# design.net
KiCad netlist of a schematic drawn in Altium Designer
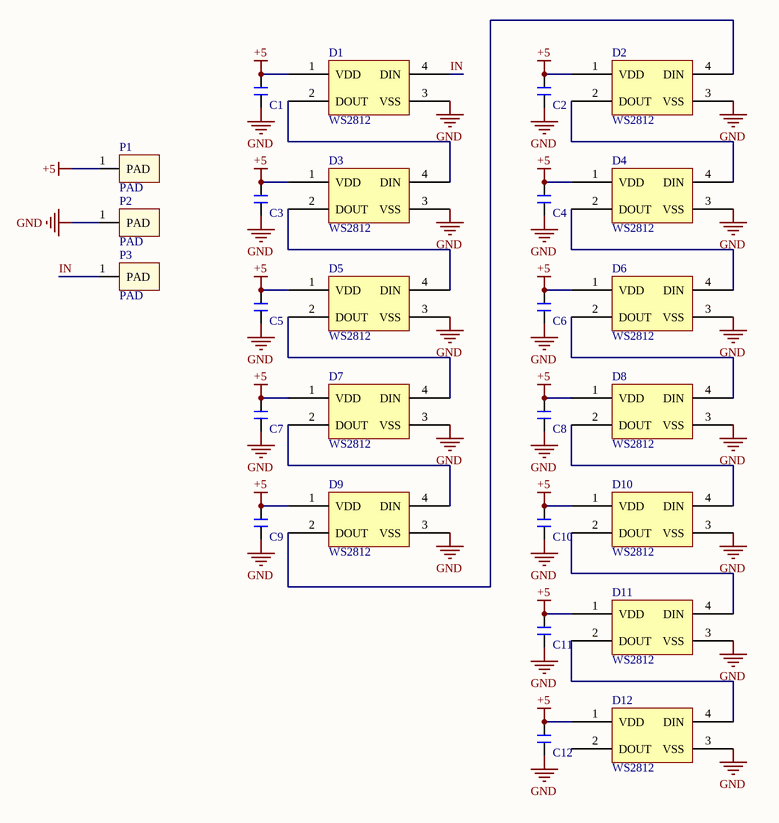
[diagram p0: 光圈图纸.SchDoc]

(export (version "E")
  (design (tool "Eeschema 10.0.6"))
  (components
    (comp (ref "C1") (value "cap") (footprint "0603c") (libsource (lib "元件库") (part "CAP")))
    (comp (ref "C2") (value "cap") (footprint "0603c") (libsource (lib "元件库") (part "CAP")))
    (comp (ref "C3") (value "cap") (footprint "0603c") (libsource (lib "元件库") (part "CAP")))
    (comp (ref "C4") (value "cap") (footprint "0603c") (libsource (lib "元件库") (part "CAP")))
    (comp (ref "C5") (value "cap") (footprint "0603c") (libsource (lib "元件库") (part "CAP")))
    (comp (ref "C6") (value "cap") (footprint "0603c") (libsource (lib "元件库") (part "CAP")))
    (comp (ref "C7") (value "cap") (footprint "0603c") (libsource (lib "元件库") (part "CAP")))
    (comp (ref "C8") (value "cap") (footprint "0603c") (libsource (lib "元件库") (part "CAP")))
    (comp (ref "C9") (value "cap") (footprint "0603c") (libsource (lib "元件库") (part "CAP")))
    (comp (ref "C10") (value "cap") (footprint "0603c") (libsource (lib "元件库") (part "CAP")))
    (comp (ref "C11") (value "cap") (footprint "0603c") (libsource (lib "元件库") (part "CAP")))
    (comp (ref "C12") (value "cap") (footprint "0603c") (libsource (lib "元件库") (part "CAP")))
    (comp (ref "D1") (value "WS2812") (footprint "WS2812") (libsource (lib "元件库") (part "WS2812")))
    (comp (ref "D2") (value "WS2812") (footprint "WS2812") (libsource (lib "元件库") (part "WS2812")))
    (comp (ref "D3") (value "WS2812") (footprint "WS2812") (libsource (lib "元件库") (part "WS2812")))
    (comp (ref "D4") (value "WS2812") (footprint "WS2812") (libsource (lib "元件库") (part "WS2812")))
    (comp (ref "D5") (value "WS2812") (footprint "WS2812") (libsource (lib "元件库") (part "WS2812")))
    (comp (ref "D6") (value "WS2812") (footprint "WS2812") (libsource (lib "元件库") (part "WS2812")))
    (comp (ref "D7") (value "WS2812") (footprint "WS2812") (libsource (lib "元件库") (part "WS2812")))
    (comp (ref "D8") (value "WS2812") (footprint "WS2812") (libsource (lib "元件库") (part "WS2812")))
    (comp (ref "D9") (value "WS2812") (footprint "WS2812") (libsource (lib "元件库") (part "WS2812")))
    (comp (ref "D10") (value "WS2812") (footprint "WS2812") (libsource (lib "元件库") (part "WS2812")))
    (comp (ref "D11") (value "WS2812") (footprint "WS2812") (libsource (lib "元件库") (part "WS2812")))
    (comp (ref "D12") (value "WS2812") (footprint "WS2812") (libsource (lib "元件库") (part "WS2812")))
    (comp (ref "P1") (value "PAD") (footprint "PAD") (libsource (lib "Schlib1") (part "PAD")))
    (comp (ref "P2") (value "PAD") (footprint "PAD") (libsource (lib "Schlib1") (part "PAD")))
    (comp (ref "P3") (value "PAD") (footprint "PAD") (libsource (lib "Schlib1") (part "PAD")))
  )
  (nets
    (net (code "1") (name "+5") (class "Default")
      (node (ref "C1") (pin "2") (pinfunction "2_2") (pintype "passive"))
      (node (ref "C10") (pin "2") (pinfunction "2_2") (pintype "passive"))
      (node (ref "C11") (pin "2") (pinfunction "2_2") (pintype "passive"))
      (node (ref "C12") (pin "2") (pinfunction "2_2") (pintype "passive"))
      (node (ref "C2") (pin "2") (pinfunction "2_2") (pintype "passive"))
      (node (ref "C3") (pin "2") (pinfunction "2_2") (pintype "passive"))
      (node (ref "C4") (pin "2") (pinfunction "2_2") (pintype "passive"))
      (node (ref "C5") (pin "2") (pinfunction "2_2") (pintype "passive"))
      (node (ref "C6") (pin "2") (pinfunction "2_2") (pintype "passive"))
      (node (ref "C7") (pin "2") (pinfunction "2_2") (pintype "passive"))
      (node (ref "C8") (pin "2") (pinfunction "2_2") (pintype "passive"))
      (node (ref "C9") (pin "2") (pinfunction "2_2") (pintype "passive"))
      (node (ref "D1") (pin "1") (pinfunction "VDD_1") (pintype "passive"))
      (node (ref "D10") (pin "1") (pinfunction "VDD_1") (pintype "passive"))
      (node (ref "D11") (pin "1") (pinfunction "VDD_1") (pintype "passive"))
      (node (ref "D12") (pin "1") (pinfunction "VDD_1") (pintype "passive"))
      (node (ref "D2") (pin "1") (pinfunction "VDD_1") (pintype "passive"))
      (node (ref "D3") (pin "1") (pinfunction "VDD_1") (pintype "passive"))
      (node (ref "D4") (pin "1") (pinfunction "VDD_1") (pintype "passive"))
      (node (ref "D5") (pin "1") (pinfunction "VDD_1") (pintype "passive"))
      (node (ref "D6") (pin "1") (pinfunction "VDD_1") (pintype "passive"))
      (node (ref "D7") (pin "1") (pinfunction "VDD_1") (pintype "passive"))
      (node (ref "D8") (pin "1") (pinfunction "VDD_1") (pintype "passive"))
      (node (ref "D9") (pin "1") (pinfunction "VDD_1") (pintype "passive"))
      (node (ref "P1") (pin "1") (pinfunction "PAD_1") (pintype "passive"))
    )
    (net (code "2") (name "/IN") (class "Default")
      (node (ref "D1") (pin "4") (pinfunction "DIN_4") (pintype "passive"))
      (node (ref "P3") (pin "1") (pinfunction "PAD_1") (pintype "passive"))
    )
    (net (code "3") (name "GND") (class "Default")
      (node (ref "C1") (pin "1") (pinfunction "1_1") (pintype "passive"))
      (node (ref "C10") (pin "1") (pinfunction "1_1") (pintype "passive"))
      (node (ref "C11") (pin "1") (pinfunction "1_1") (pintype "passive"))
      (node (ref "C12") (pin "1") (pinfunction "1_1") (pintype "passive"))
      (node (ref "C2") (pin "1") (pinfunction "1_1") (pintype "passive"))
      (node (ref "C3") (pin "1") (pinfunction "1_1") (pintype "passive"))
      (node (ref "C4") (pin "1") (pinfunction "1_1") (pintype "passive"))
      (node (ref "C5") (pin "1") (pinfunction "1_1") (pintype "passive"))
      (node (ref "C6") (pin "1") (pinfunction "1_1") (pintype "passive"))
      (node (ref "C7") (pin "1") (pinfunction "1_1") (pintype "passive"))
      (node (ref "C8") (pin "1") (pinfunction "1_1") (pintype "passive"))
      (node (ref "C9") (pin "1") (pinfunction "1_1") (pintype "passive"))
      (node (ref "D1") (pin "3") (pinfunction "VSS_3") (pintype "passive"))
      (node (ref "D10") (pin "3") (pinfunction "VSS_3") (pintype "passive"))
      (node (ref "D11") (pin "3") (pinfunction "VSS_3") (pintype "passive"))
      (node (ref "D12") (pin "3") (pinfunction "VSS_3") (pintype "passive"))
      (node (ref "D2") (pin "3") (pinfunction "VSS_3") (pintype "passive"))
      (node (ref "D3") (pin "3") (pinfunction "VSS_3") (pintype "passive"))
      (node (ref "D4") (pin "3") (pinfunction "VSS_3") (pintype "passive"))
      (node (ref "D5") (pin "3") (pinfunction "VSS_3") (pintype "passive"))
      (node (ref "D6") (pin "3") (pinfunction "VSS_3") (pintype "passive"))
      (node (ref "D7") (pin "3") (pinfunction "VSS_3") (pintype "passive"))
      (node (ref "D8") (pin "3") (pinfunction "VSS_3") (pintype "passive"))
      (node (ref "D9") (pin "3") (pinfunction "VSS_3") (pintype "passive"))
      (node (ref "P2") (pin "1") (pinfunction "PAD_1") (pintype "passive"))
    )
    (net (code "4") (name "Net-(D1-DOUT)") (class "Default")
      (node (ref "D1") (pin "2") (pinfunction "DOUT_2") (pintype "passive"))
      (node (ref "D3") (pin "4") (pinfunction "DIN_4") (pintype "passive"))
    )
    (net (code "5") (name "Net-(D2-DIN)") (class "Default")
      (node (ref "D2") (pin "4") (pinfunction "DIN_4") (pintype "passive"))
      (node (ref "D9") (pin "2") (pinfunction "DOUT_2") (pintype "passive"))
    )
    (net (code "6") (name "Net-(D2-DOUT)") (class "Default")
      (node (ref "D2") (pin "2") (pinfunction "DOUT_2") (pintype "passive"))
      (node (ref "D4") (pin "4") (pinfunction "DIN_4") (pintype "passive"))
    )
    (net (code "7") (name "Net-(D3-DOUT)") (class "Default")
      (node (ref "D3") (pin "2") (pinfunction "DOUT_2") (pintype "passive"))
      (node (ref "D5") (pin "4") (pinfunction "DIN_4") (pintype "passive"))
    )
    (net (code "8") (name "Net-(D4-DOUT)") (class "Default")
      (node (ref "D4") (pin "2") (pinfunction "DOUT_2") (pintype "passive"))
      (node (ref "D6") (pin "4") (pinfunction "DIN_4") (pintype "passive"))
    )
    (net (code "9") (name "Net-(D5-DOUT)") (class "Default")
      (node (ref "D5") (pin "2") (pinfunction "DOUT_2") (pintype "passive"))
      (node (ref "D7") (pin "4") (pinfunction "DIN_4") (pintype "passive"))
    )
    (net (code "10") (name "Net-(D6-DOUT)") (class "Default")
      (node (ref "D6") (pin "2") (pinfunction "DOUT_2") (pintype "passive"))
      (node (ref "D8") (pin "4") (pinfunction "DIN_4") (pintype "passive"))
    )
    (net (code "11") (name "Net-(D7-DOUT)") (class "Default")
      (node (ref "D7") (pin "2") (pinfunction "DOUT_2") (pintype "passive"))
      (node (ref "D9") (pin "4") (pinfunction "DIN_4") (pintype "passive"))
    )
    (net (code "12") (name "Net-(D10-DIN)") (class "Default")
      (node (ref "D10") (pin "4") (pinfunction "DIN_4") (pintype "passive"))
      (node (ref "D8") (pin "2") (pinfunction "DOUT_2") (pintype "passive"))
    )
    (net (code "13") (name "Net-(D10-DOUT)") (class "Default")
      (node (ref "D10") (pin "2") (pinfunction "DOUT_2") (pintype "passive"))
      (node (ref "D11") (pin "4") (pinfunction "DIN_4") (pintype "passive"))
    )
    (net (code "14") (name "Net-(D11-DOUT)") (class "Default")
      (node (ref "D11") (pin "2") (pinfunction "DOUT_2") (pintype "passive"))
      (node (ref "D12") (pin "4") (pinfunction "DIN_4") (pintype "passive"))
    )
    (net (code "15") (name "unconnected-(D12-DOUT-Pad2)") (class "Default")
      (node (ref "D12") (pin "2") (pinfunction "DOUT_2") (pintype "passive"))
    )
  )
)
